# RS485.net
KiCad netlist of a schematic drawn in Altium Designer
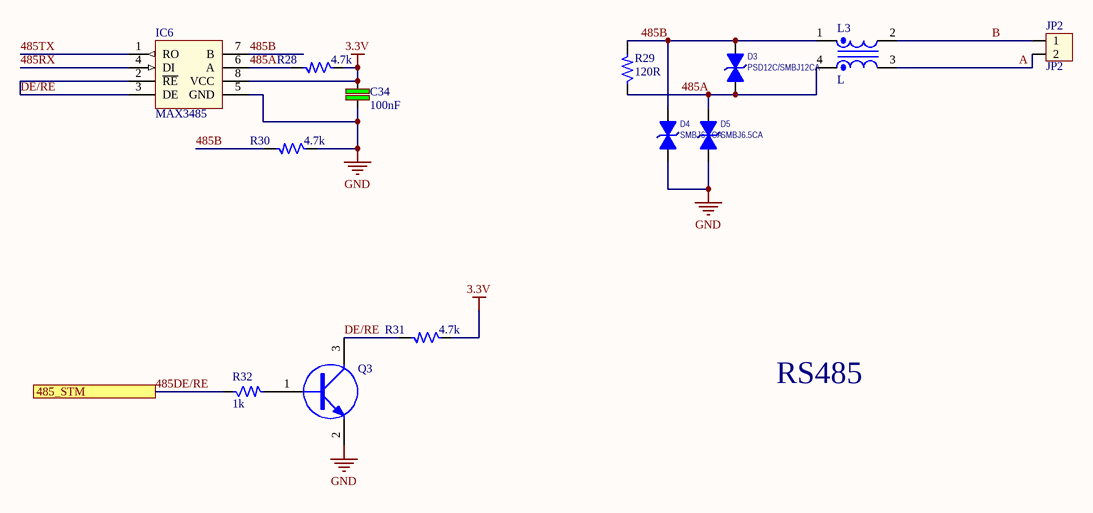
[diagram p0: RS485.SchDoc]

(export (version "E")
  (design (tool "Eeschema 10.0.6"))
  (components
    (comp (ref "C34")
      (value "100nF")
      (footprint "C-0805")
      (description "Cap SMD")
      (fields
        (field (name "MANUFACTURER") "Samsung Electro-Mechanics")
        (field (name "PART NUMBER") "CL21B104KBCNNWC")
      )
      (libsource (lib "Anh_Trung") (part "C"))
    )
    (comp (ref "D3")
      (value "PSD12C/SMBJ12CA")
      (footprint "SOD323 - DO241")
      (description "TVS DIODE 30VWM 48.4VC SMA")
      (fields (field (name "MANUFACTURER") "Bourns Inc.") (field (name "PART NUMBER") "PSD12C"))
      (libsource (lib "Anh_Trung") (part "SMAJ30CA-30V/8.3A"))
    )
    (comp (ref "D4")
      (value "SMBJ6.5CA")
      (footprint "TVS")
      (description "TVS DIODE 30VWM 48.4VC SMA")
      (fields (field (name "MANUFACTURER") "Bourns Inc.") (field (name "PART NUMBER") "PSD12C"))
      (libsource (lib "Anh_Trung") (part "SMAJ30CA-30V/8.3A"))
    )
    (comp (ref "D5")
      (value "SMBJ6.5CA")
      (footprint "TVS")
      (description "TVS DIODE 30VWM 48.4VC SMA")
      (fields (field (name "MANUFACTURER") "Bourns Inc.") (field (name "PART NUMBER") "PSD12C"))
      (libsource (lib "Anh_Trung") (part "SMAJ30CA-30V/8.3A"))
    )
    (comp (ref "IC6")
      (value "MAX3485")
      (footprint "SOIC-8")
      (description "IC TRANSCEIVER HALF 1/1 SOT23-8")
      (fields (field (name "MANUFACTURER") "Maxim Integrated") (field (name "PART NUMBER") "MAX3362EKA+T"))
      (libsource (lib "Anh_Trung") (part "MAX3362EKA+T"))
    )
    (comp (ref "JP2")
      (value "JP2")
      (footprint "KF2-5.08")
      (description "Connector 2")
      (libsource (lib "Anh_Trung") (part "Con2"))
    )
    (comp (ref "L3")
      (value "L")
      (footprint "CMC 51UH 800MA 2LN SMD AEC-Q200")
      (description "CMC 51UH 800MA 2LN SMD AEC-Q200")
      (fields
        (field (name "MANUFACTURER") "EPCOS - TDK Electronics")
        (field (name "PART NUMBER") "B82793S0513N201")
      )
      (libsource (lib "Anh_Trung") (part "L filter Common Mode Chokes"))
    )
    (comp (ref "Q3")
      (value "C1815(MMBT4401)")
      (footprint "SOT23")
      (description "Transistor C1815, SOT23")
      (fields (field (name "MANUFACTURER") "Fairchild Semiconductor") (field (name "PART NUMBER") "MMBT4401"))
      (libsource (lib "Anh_Trung") (part "NPN"))
    )
    (comp (ref "R28")
      (value "4.7k")
      (footprint "R-0805")
      (description "RES SMD 4.7K OHM 1% 1/8W 0805")
      (fields (field (name "MANUFACTURER") "Yageo") (field (name "PART NUMBER") "RC0805FR-074K7L"))
      (libsource (lib "Anh_Trung") (part "R"))
    )
    (comp (ref "R29")
      (value "120R")
      (footprint "R-0805")
      (description "Resistor 1/4W")
      (fields (field (name "MANUFACTURER") "Yageo") (field (name "PART NUMBER") "RC0805FR-07120RL"))
      (libsource (lib "Anh_Trung") (part "R"))
    )
    (comp (ref "R30")
      (value "4.7k")
      (footprint "R-0805")
      (description "RES SMD 4.7K OHM 1% 1/8W 0805")
      (fields (field (name "MANUFACTURER") "Yageo") (field (name "PART NUMBER") "RC0805FR-074K7L"))
      (libsource (lib "Anh_Trung") (part "R"))
    )
    (comp (ref "R31")
      (value "4.7k")
      (footprint "R-0805")
      (description "RES SMD 4.7K OHM 1% 1/8W 0805")
      (fields (field (name "MANUFACTURER") "Yageo") (field (name "PART NUMBER") "RC0805FR-074K7L"))
      (libsource (lib "Anh_Trung") (part "R"))
    )
    (comp (ref "R32")
      (value "1k")
      (footprint "R-0805")
      (description "Resistor 1/4W")
      (fields (field (name "MANUFACTURER") "Yageo") (field (name "PART NUMBER") "RC0805FR-071KL"))
      (libsource (lib "Anh_Trung") (part "R"))
    )
  )
  (nets
    (net (code "1") (name "/485A") (class "Default")
      (node (ref "D3") (pin "1") (pinfunction "A_1") (pintype "passive"))
      (node (ref "D5") (pin "2") (pinfunction "K_2") (pintype "passive"))
      (node (ref "IC6") (pin "6") (pinfunction "A_6") (pintype "passive"))
      (node (ref "L3") (pin "4") (pintype "passive"))
      (node (ref "R28") (pin "2") (pinfunction "2_2") (pintype "passive"))
      (node (ref "R29") (pin "1") (pinfunction "1_1") (pintype "passive"))
    )
    (net (code "2") (name "/485B") (class "Default")
      (node (ref "D3") (pin "2") (pinfunction "K_2") (pintype "passive"))
      (node (ref "D4") (pin "2") (pinfunction "K_2") (pintype "passive"))
      (node (ref "IC6") (pin "7") (pinfunction "B_7") (pintype "passive"))
      (node (ref "L3") (pin "1") (pintype "passive"))
      (node (ref "R29") (pin "2") (pinfunction "2_2") (pintype "passive"))
      (node (ref "R30") (pin "2") (pinfunction "2_2") (pintype "passive"))
    )
    (net (code "3") (name "/485DE{slash}RE") (class "Default")
      (node (ref "R32") (pin "1") (pinfunction "1_1") (pintype "passive"))
    )
    (net (code "4") (name "/485RX") (class "Default")
      (node (ref "IC6") (pin "4") (pinfunction "DI_4") (pintype "input"))
    )
    (net (code "5") (name "/485TX") (class "Default")
      (node (ref "IC6") (pin "1") (pinfunction "RO_1") (pintype "output"))
    )
    (net (code "6") (name "/A") (class "Default")
      (node (ref "JP2") (pin "2") (pinfunction "2_2") (pintype "passive"))
      (node (ref "L3") (pin "3") (pintype "passive"))
    )
    (net (code "7") (name "/B") (class "Default")
      (node (ref "JP2") (pin "1") (pinfunction "1_1") (pintype "passive"))
      (node (ref "L3") (pin "2") (pintype "passive"))
    )
    (net (code "8") (name "/DE{slash}RE") (class "Default")
      (node (ref "IC6") (pin "2") (pinfunction "~{RE}_2") (pintype "passive"))
      (node (ref "IC6") (pin "3") (pinfunction "DE_3") (pintype "passive"))
      (node (ref "Q3") (pin "3") (pinfunction "C_3") (pintype "passive"))
      (node (ref "R31") (pin "2") (pinfunction "2_2") (pintype "passive"))
    )
    (net (code "9") (name "3.3V") (class "Default")
      (node (ref "C34") (pin "1") (pinfunction "1_1") (pintype "passive"))
      (node (ref "IC6") (pin "8") (pinfunction "VCC_8") (pintype "passive"))
      (node (ref "R28") (pin "1") (pinfunction "1_1") (pintype "passive"))
      (node (ref "R31") (pin "1") (pinfunction "1_1") (pintype "passive"))
    )
    (net (code "10") (name "GND") (class "Default")
      (node (ref "C34") (pin "2") (pinfunction "2_2") (pintype "passive"))
      (node (ref "D4") (pin "1") (pinfunction "A_1") (pintype "passive"))
      (node (ref "D5") (pin "1") (pinfunction "A_1") (pintype "passive"))
      (node (ref "IC6") (pin "5") (pinfunction "GND_5") (pintype "passive"))
      (node (ref "Q3") (pin "2") (pinfunction "E_2") (pintype "passive"))
      (node (ref "R30") (pin "1") (pinfunction "1_1") (pintype "passive"))
    )
    (net (code "11") (name "Net-(Q3-B)") (class "Default")
      (node (ref "Q3") (pin "1") (pinfunction "B_1") (pintype "passive"))
      (node (ref "R32") (pin "2") (pinfunction "2_2") (pintype "passive"))
    )
  )
)
